# 3-1.net
KiCad netlist of a schematic drawn in Altium Designer
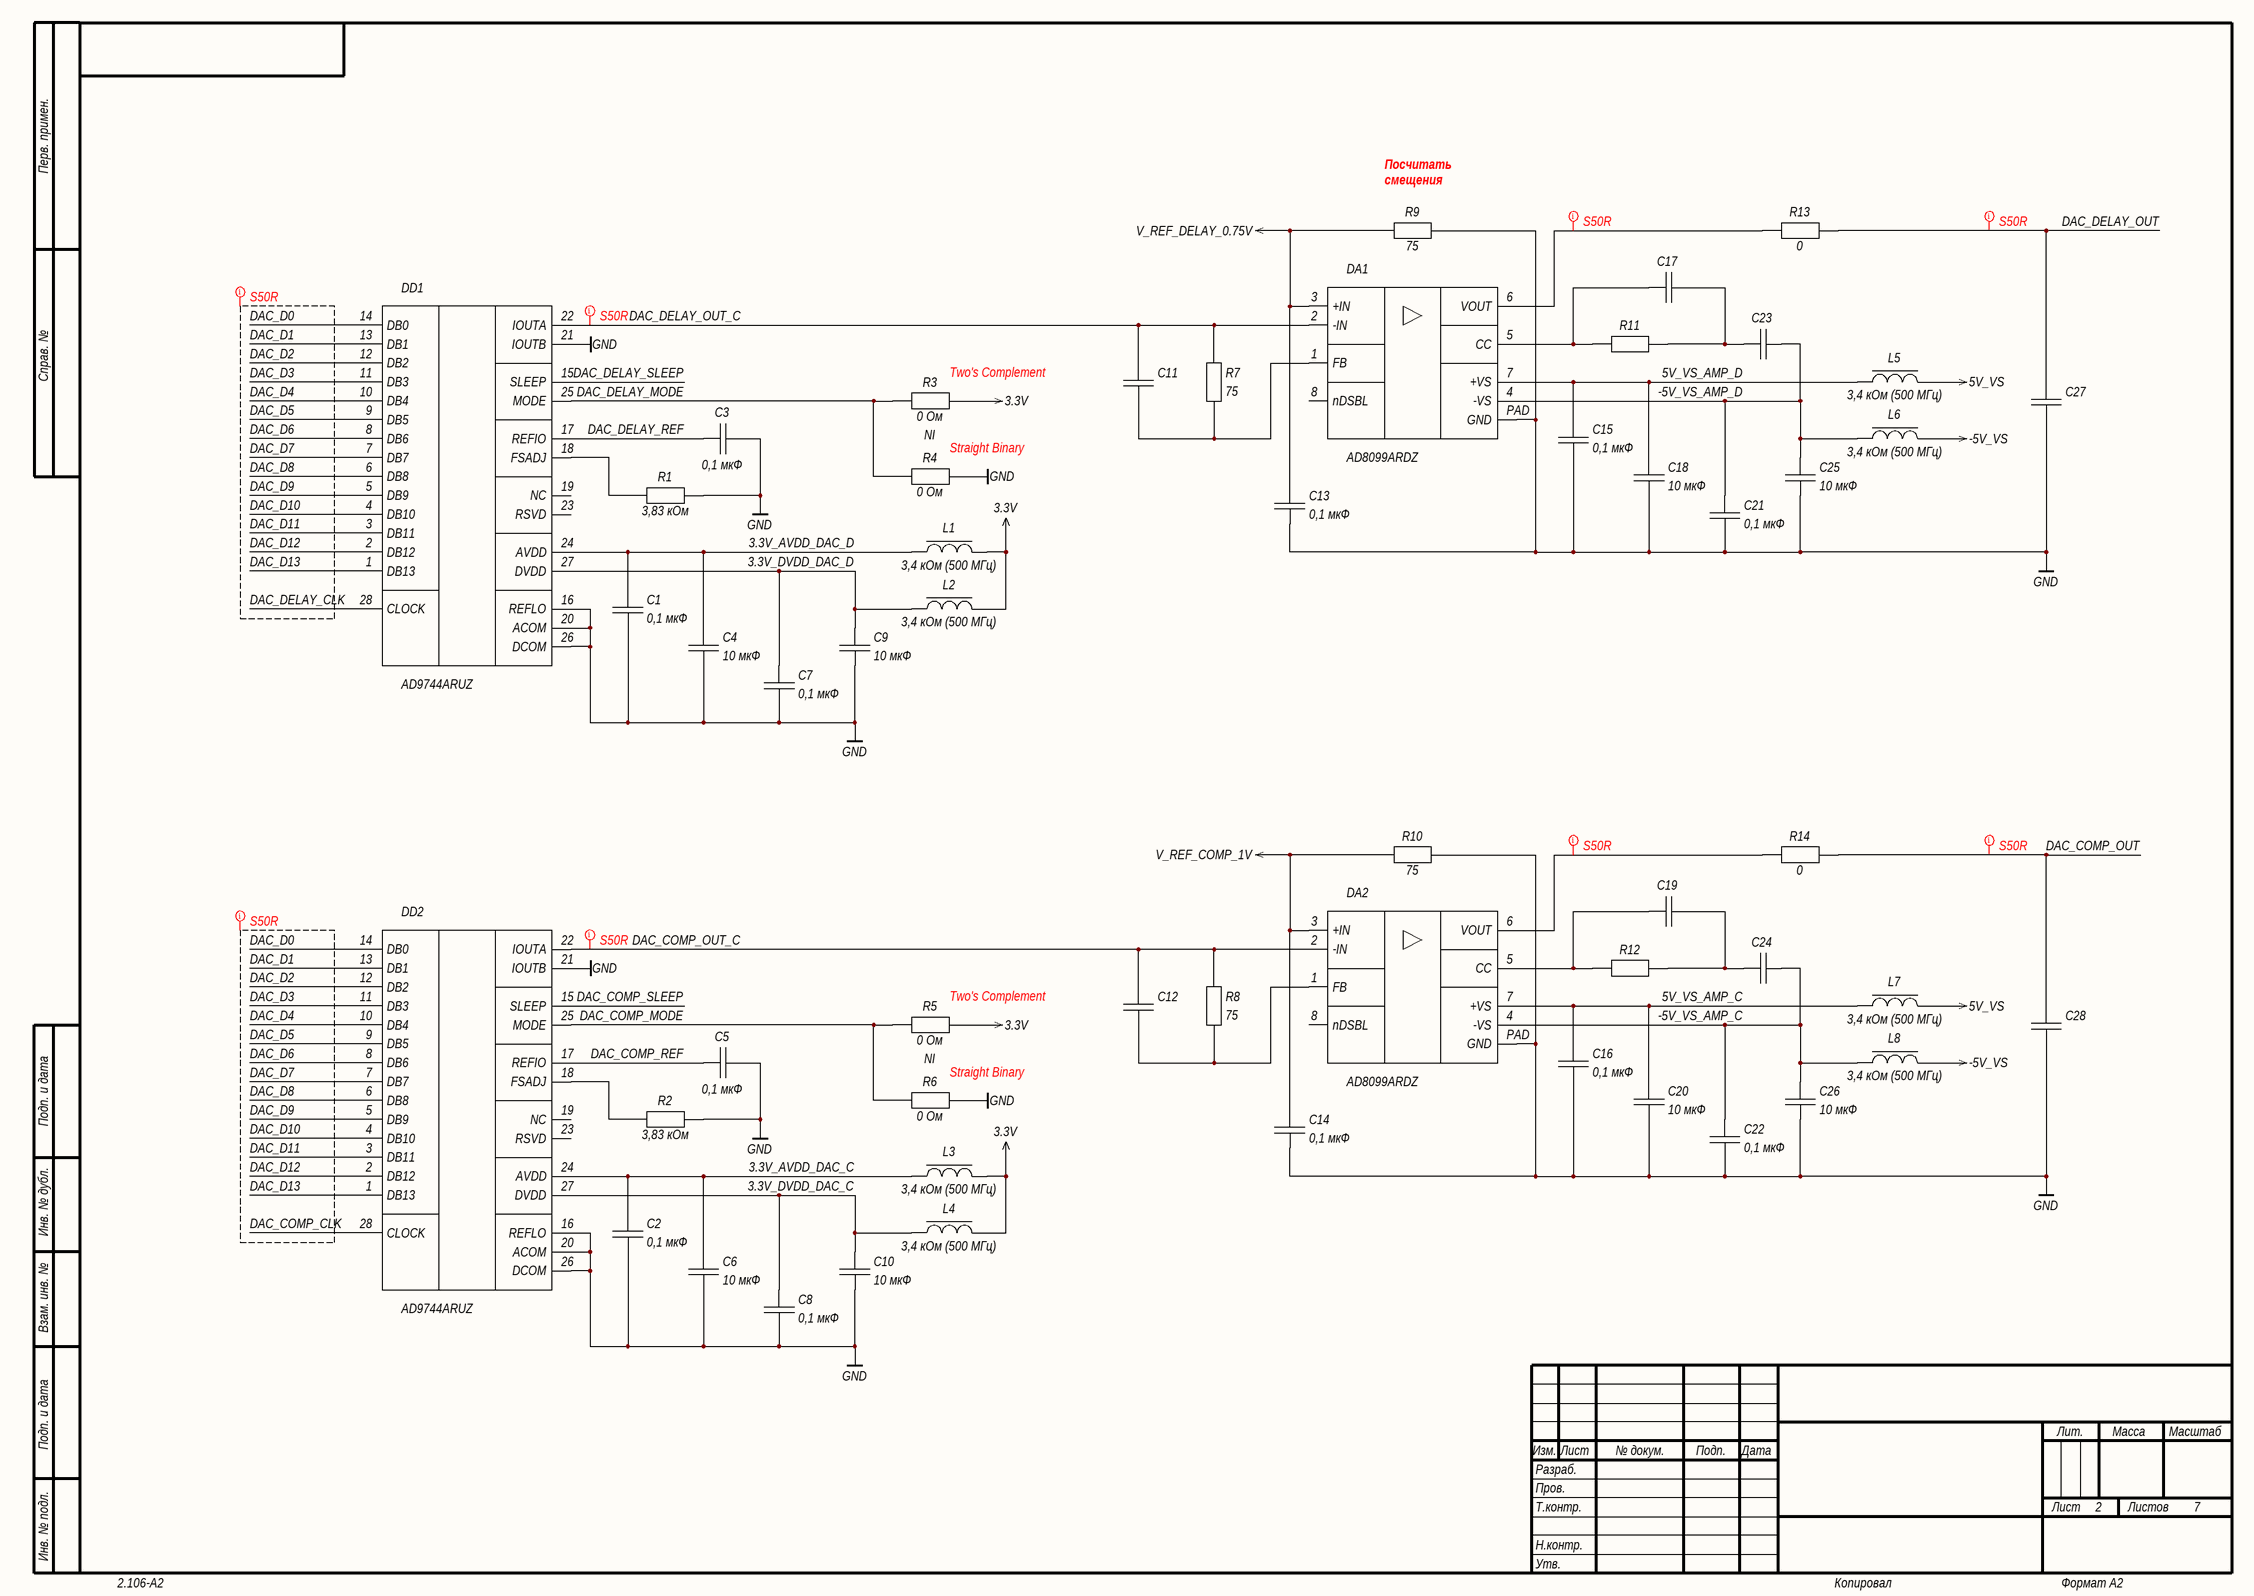
[diagram p0: Э3-1 УВ ЦАП.SchDoc]

(export (version "E")
  (design (tool "Eeschema 10.0.6"))
  (components
    (comp (ref "C1")
      (value "0,1 мкФ")
      (footprint "C0402-B-0.5mm")
      (description "0402 X7R 0,1 мкФ ±10 % 50 В")
      (fields (field (name "PARTNUMBER") "GRM155R71H104KE14D"))
      (libsource (lib "Capacitors") (part "Non Polar Ver."))
    )
    (comp (ref "C2")
      (value "0,1 мкФ")
      (footprint "C0402-B-0.5mm")
      (description "0402 X7R 0,1 мкФ ±10 % 50 В")
      (fields (field (name "PARTNUMBER") "GRM155R71H104KE14D"))
      (libsource (lib "Capacitors") (part "Non Polar Ver."))
    )
    (comp (ref "C3")
      (value "0,1 мкФ")
      (footprint "C0402-B-0.5mm")
      (description "0402 X7R 0,1 мкФ ±10 % 50 В")
      (fields (field (name "PARTNUMBER") "GRM155R71H104KE14D"))
      (libsource (lib "Capacitors") (part "Non Polar Hor."))
    )
    (comp (ref "C4")
      (value "10 мкФ")
      (footprint "C0603-B-0.8mm")
      (description "0603 X5R 10 мкФ ±20 % 25 В")
      (fields (field (name "PARTNUMBER") "GRM188R61E106MA73"))
      (libsource (lib "Capacitors") (part "Non Polar Ver."))
    )
    (comp (ref "C5")
      (value "0,1 мкФ")
      (footprint "C0402-B-0.5mm")
      (description "0402 X7R 0,1 мкФ ±10 % 50 В")
      (fields (field (name "PARTNUMBER") "GRM155R71H104KE14D"))
      (libsource (lib "Capacitors") (part "Non Polar Hor."))
    )
    (comp (ref "C6")
      (value "10 мкФ")
      (footprint "C0603-B-0.8mm")
      (description "0603 X5R 10 мкФ ±20 % 25 В")
      (fields (field (name "PARTNUMBER") "GRM188R61E106MA73"))
      (libsource (lib "Capacitors") (part "Non Polar Ver."))
    )
    (comp (ref "C7")
      (value "0,1 мкФ")
      (footprint "C0402-B-0.5mm")
      (description "0402 X7R 0,1 мкФ ±10 % 50 В")
      (fields (field (name "PARTNUMBER") "GRM155R71H104KE14D"))
      (libsource (lib "Capacitors") (part "Non Polar Ver."))
    )
    (comp (ref "C8")
      (value "0,1 мкФ")
      (footprint "C0402-B-0.5mm")
      (description "0402 X7R 0,1 мкФ ±10 % 50 В")
      (fields (field (name "PARTNUMBER") "GRM155R71H104KE14D"))
      (libsource (lib "Capacitors") (part "Non Polar Ver."))
    )
    (comp (ref "C9")
      (value "10 мкФ")
      (footprint "C0603-B-0.8mm")
      (description "0603 X5R 10 мкФ ±20 % 25 В")
      (fields (field (name "PARTNUMBER") "GRM188R61E106MA73"))
      (libsource (lib "Capacitors") (part "Non Polar Ver."))
    )
    (comp (ref "C10")
      (value "10 мкФ")
      (footprint "C0603-B-0.8mm")
      (description "GRM188R61E106MA73")
      (libsource (lib "Capacitors") (part "Non Polar Ver."))
    )
    (comp (ref "C11")
      (value "~")
      (footprint "C0402-B-0.5mm")
      (libsource (lib "Capacitors") (part "Non Polar Ver."))
    )
    (comp (ref "C12")
      (value "~")
      (footprint "C0402-B-0.5mm")
      (libsource (lib "Capacitors") (part "Non Polar Ver."))
    )
    (comp (ref "C13")
      (value "0,1 мкФ")
      (footprint "C0402-B-0.5mm")
      (description "0402 X7R 0,1 мкФ ±10 % 50 В")
      (fields (field (name "PARTNUMBER") "GRM155R71H104KE14D"))
      (libsource (lib "Capacitors") (part "Non Polar Ver."))
    )
    (comp (ref "C14")
      (value "0,1 мкФ")
      (footprint "C0402-B-0.5mm")
      (description "0402 X7R 0,1 мкФ ±10 % 50 В")
      (fields (field (name "PARTNUMBER") "GRM155R71H104KE14D"))
      (libsource (lib "Capacitors") (part "Non Polar Ver."))
    )
    (comp (ref "C15")
      (value "0,1 мкФ")
      (footprint "C0402-B-0.5mm")
      (description "0402 X7R 0,1 мкФ ±10 % 50 В")
      (fields (field (name "PARTNUMBER") "GRM155R71H104KE14D"))
      (libsource (lib "Capacitors") (part "Non Polar Ver."))
    )
    (comp (ref "C16")
      (value "0,1 мкФ")
      (footprint "C0402-B-0.5mm")
      (description "0402 X7R 0,1 мкФ ±10 % 50 В")
      (fields (field (name "PARTNUMBER") "GRM155R71H104KE14D"))
      (libsource (lib "Capacitors") (part "Non Polar Ver."))
    )
    (comp (ref "C17")
      (value "~")
      (footprint "C0402-B-0.5mm")
      (libsource (lib "Capacitors") (part "Non Polar Hor."))
    )
    (comp (ref "C18")
      (value "10 мкФ")
      (footprint "C0603-B-0.8mm")
      (description "0603 X5R 10 мкФ ±20 % 25 В")
      (fields (field (name "PARTNUMBER") "GRM188R61E106MA73"))
      (libsource (lib "Capacitors") (part "Non Polar Ver."))
    )
    (comp (ref "C19")
      (value "~")
      (footprint "C0402-B-0.5mm")
      (libsource (lib "Capacitors") (part "Non Polar Hor."))
    )
    (comp (ref "C20")
      (value "10 мкФ")
      (footprint "C0603-B-0.8mm")
      (description "0603 X5R 10 мкФ ±20 % 25 В")
      (fields (field (name "PARTNUMBER") "GRM188R61E106MA73"))
      (libsource (lib "Capacitors") (part "Non Polar Ver."))
    )
    (comp (ref "C21")
      (value "0,1 мкФ")
      (footprint "C0402-B-0.5mm")
      (description "0402 X7R 0,1 мкФ ±10 % 50 В")
      (fields (field (name "PARTNUMBER") "GRM155R71H104KE14D"))
      (libsource (lib "Capacitors") (part "Non Polar Ver."))
    )
    (comp (ref "C22")
      (value "0,1 мкФ")
      (footprint "C0402-B-0.5mm")
      (description "0402 X7R 0,1 мкФ ±10 % 50 В")
      (fields (field (name "PARTNUMBER") "GRM155R71H104KE14D"))
      (libsource (lib "Capacitors") (part "Non Polar Ver."))
    )
    (comp (ref "C23")
      (value "~")
      (footprint "C0402-B-0.5mm")
      (libsource (lib "Capacitors") (part "Non Polar Hor."))
    )
    (comp (ref "C24")
      (value "~")
      (footprint "C0402-B-0.5mm")
      (libsource (lib "Capacitors") (part "Non Polar Hor."))
    )
    (comp (ref "C25")
      (value "10 мкФ")
      (footprint "C0603-B-0.8mm")
      (description "0603 X5R 10 мкФ ±20 % 25 В")
      (fields (field (name "PARTNUMBER") "GRM188R61E106MA73"))
      (libsource (lib "Capacitors") (part "Non Polar Ver."))
    )
    (comp (ref "C26")
      (value "10 мкФ")
      (footprint "C0603-B-0.8mm")
      (description "0603 X5R 10 мкФ ±20 % 25 В")
      (fields (field (name "PARTNUMBER") "GRM188R61E106MA73"))
      (libsource (lib "Capacitors") (part "Non Polar Ver."))
    )
    (comp (ref "C27")
      (value "~")
      (footprint "C0402-B-0.5mm")
      (libsource (lib "Capacitors") (part "Non Polar Ver."))
    )
    (comp (ref "C28")
      (value "~")
      (footprint "C0402-B-0.5mm")
      (libsource (lib "Capacitors") (part "Non Polar Ver."))
    )
    (comp (ref "DA1")
      (value "AD8099ARDZ")
      (footprint "8-SOIC-EP-3.9")
      (description "Ultralow Distortion, High Speed, 0.95 nV/√Hz Voltage Noise Op Amp")
      (fields (field (name "MANUFACTURER") "Analog Devices, Inc."))
      (libsource (lib "Analog") (part "AD8099ARDZ"))
    )
    (comp (ref "DA2")
      (value "AD8099ARDZ")
      (footprint "8-SOIC-EP-3.9")
      (description "Ultralow Distortion, High Speed, 0.95 nV/√Hz Voltage Noise Op Amp")
      (fields (field (name "MANUFACTURER") "Analog Devices, Inc."))
      (libsource (lib "Analog") (part "AD8099ARDZ"))
    )
    (comp (ref "DD1")
      (value "AD9744ARUZ")
      (footprint "28-TSSOP-4.4")
      (description "14-Bit, 210 MSPS TxDAC®\r\nD/A Converter")
      (fields (field (name "MANUFACTURER") "Analog Devices"))
      (libsource (lib "Digital") (part "AD9744ARUZ"))
    )
    (comp (ref "DD2")
      (value "AD9744ARUZ")
      (footprint "28-TSSOP-4.4")
      (description "14-Bit, 210 MSPS TxDAC®\r\nD/A Converter")
      (fields (field (name "MANUFACTURER") "Analog Devices"))
      (libsource (lib "Digital") (part "AD9744ARUZ"))
    )
    (comp (ref "L1")
      (value "3,4 кОм (500 МГц)")
      (footprint "L0402-B-0.5mm")
      (fields (field (name "PARTNUMBER") "BLM15HD182BH1"))
      (libsource (lib "Inductors") (part "Inductor MC Hor."))
    )
    (comp (ref "L2")
      (value "3,4 кОм (500 МГц)")
      (footprint "L0402-B-0.5mm")
      (fields (field (name "PARTNUMBER") "BLM15HD182BH1"))
      (libsource (lib "Inductors") (part "Inductor MC Hor."))
    )
    (comp (ref "L3")
      (value "3,4 кОм (500 МГц)")
      (footprint "L0402-B-0.5mm")
      (fields (field (name "PARTNUMBER") "BLM15HD182BH1"))
      (libsource (lib "Inductors") (part "Inductor MC Hor."))
    )
    (comp (ref "L4")
      (value "3,4 кОм (500 МГц)")
      (footprint "L0402-B-0.5mm")
      (fields (field (name "PARTNUMBER") "BLM15HD182BH1"))
      (libsource (lib "Inductors") (part "Inductor MC Hor."))
    )
    (comp (ref "L5")
      (value "3,4 кОм (500 МГц)")
      (footprint "L0402-B-0.5mm")
      (fields (field (name "PARTNUMBER") "BLM15HD182BH1"))
      (libsource (lib "Inductors") (part "Inductor MC Hor."))
    )
    (comp (ref "L6")
      (value "3,4 кОм (500 МГц)")
      (footprint "L0402-B-0.5mm")
      (fields (field (name "PARTNUMBER") "BLM15HD182BH1"))
      (libsource (lib "Inductors") (part "Inductor MC Hor."))
    )
    (comp (ref "L7")
      (value "3,4 кОм (500 МГц)")
      (footprint "L0402-B-0.5mm")
      (fields (field (name "PARTNUMBER") "BLM15HD182BH1"))
      (libsource (lib "Inductors") (part "Inductor MC Hor."))
    )
    (comp (ref "L8")
      (value "3,4 кОм (500 МГц)")
      (footprint "L0402-B-0.5mm")
      (fields (field (name "PARTNUMBER") "BLM15HD182BH1"))
      (libsource (lib "Inductors") (part "Inductor MC Hor."))
    )
    (comp (ref "R1")
      (value "3,83 кОм")
      (footprint "CR0402-B-0.35mm")
      (description "0402 3,83 кОм ±1 %")
      (libsource (lib "Resistors") (part "Resistor Hor."))
    )
    (comp (ref "R2")
      (value "3,83 кОм")
      (footprint "CR0402-B-0.35mm")
      (description "0402 3,83 кОм ±1 %")
      (libsource (lib "Resistors") (part "Resistor Hor."))
    )
    (comp (ref "R3")
      (value "0 Ом")
      (footprint "CR0402-B-0.35mm")
      (description "0402 0 Ом")
      (fields (field (name "COMPONENTTYPE") "NI"))
      (libsource (lib "Resistors") (part "Resistor Hor."))
    )
    (comp (ref "R4")
      (value "0 Ом")
      (footprint "CR0402-B-0.35mm")
      (libsource (lib "Resistors") (part "Resistor Hor."))
    )
    (comp (ref "R5")
      (value "0 Ом")
      (footprint "CR0402-B-0.35mm")
      (description "0402 0 Ом")
      (fields (field (name "COMPONENTTYPE") "NI"))
      (libsource (lib "Resistors") (part "Resistor Hor."))
    )
    (comp (ref "R6")
      (value "0 Ом")
      (footprint "CR0402-B-0.35mm")
      (libsource (lib "Resistors") (part "Resistor Hor."))
    )
    (comp (ref "R7")
      (value "75")
      (footprint "CR0402-B-0.35mm")
      (description "0402 75 Ом ±1 %")
      (libsource (lib "Resistors") (part "Resistor Ver."))
    )
    (comp (ref "R8")
      (value "75")
      (footprint "CR0402-B-0.35mm")
      (description "0402 75 Ом ±1 %")
      (libsource (lib "Resistors") (part "Resistor Ver."))
    )
    (comp (ref "R9")
      (value "75")
      (footprint "CR0402-B-0.35mm")
      (description "0402 75 Ом ±1 %")
      (libsource (lib "Resistors") (part "Resistor Hor."))
    )
    (comp (ref "R10")
      (value "75")
      (footprint "CR0402-B-0.35mm")
      (description "0402 75 Ом ±1 %")
      (libsource (lib "Resistors") (part "Resistor Hor."))
    )
    (comp (ref "R11")
      (value "~")
      (footprint "CR0402-B-0.35mm")
      (libsource (lib "Resistors") (part "Resistor Hor."))
    )
    (comp (ref "R12")
      (value "~")
      (footprint "CR0402-B-0.35mm")
      (libsource (lib "Resistors") (part "Resistor Hor."))
    )
    (comp (ref "R13")
      (value "0")
      (footprint "CR0402-B-0.35mm")
      (description "0402 0 Ом")
      (libsource (lib "Resistors") (part "Resistor Hor."))
    )
    (comp (ref "R14")
      (value "0")
      (footprint "CR0402-B-0.35mm")
      (description "0402 0 Ом")
      (libsource (lib "Resistors") (part "Resistor Hor."))
    )
  )
  (nets
    (net (code "1") (name "-5V_VS") (class "Default")
      (node (ref "L6") (pin "2") (pinfunction "2_2") (pintype "passive"))
      (node (ref "L8") (pin "2") (pinfunction "2_2") (pintype "passive"))
    )
    (net (code "2") (name "/-5V_VS_AMP_C") (class "Default")
      (node (ref "C22") (pin "1") (pinfunction "1_1") (pintype "passive"))
      (node (ref "C24") (pin "2") (pinfunction "2_2") (pintype "passive"))
      (node (ref "C26") (pin "1") (pinfunction "1_1") (pintype "passive"))
      (node (ref "DA2") (pin "4") (pinfunction "-VS_4") (pintype "passive"))
      (node (ref "L8") (pin "1") (pinfunction "1_1") (pintype "passive"))
    )
    (net (code "3") (name "/-5V_VS_AMP_D") (class "Default")
      (node (ref "C21") (pin "1") (pinfunction "1_1") (pintype "passive"))
      (node (ref "C23") (pin "2") (pinfunction "2_2") (pintype "passive"))
      (node (ref "C25") (pin "1") (pinfunction "1_1") (pintype "passive"))
      (node (ref "DA1") (pin "4") (pinfunction "-VS_4") (pintype "passive"))
      (node (ref "L6") (pin "1") (pinfunction "1_1") (pintype "passive"))
    )
    (net (code "4") (name "/3.3V_AVDD_DAC_C") (class "Default")
      (node (ref "C2") (pin "1") (pinfunction "1_1") (pintype "passive"))
      (node (ref "C6") (pin "1") (pinfunction "1_1") (pintype "passive"))
      (node (ref "DD2") (pin "24") (pinfunction "AVDD_24") (pintype "passive"))
      (node (ref "L3") (pin "1") (pinfunction "1_1") (pintype "passive"))
    )
    (net (code "5") (name "/3.3V_AVDD_DAC_D") (class "Default")
      (node (ref "C1") (pin "1") (pinfunction "1_1") (pintype "passive"))
      (node (ref "C4") (pin "1") (pinfunction "1_1") (pintype "passive"))
      (node (ref "DD1") (pin "24") (pinfunction "AVDD_24") (pintype "passive"))
      (node (ref "L1") (pin "1") (pinfunction "1_1") (pintype "passive"))
    )
    (net (code "6") (name "/3.3V_DVDD_DAC_C") (class "Default")
      (node (ref "C10") (pin "1") (pinfunction "1_1") (pintype "passive"))
      (node (ref "C8") (pin "1") (pinfunction "1_1") (pintype "passive"))
      (node (ref "DD2") (pin "27") (pinfunction "DVDD_27") (pintype "passive"))
      (node (ref "L4") (pin "1") (pinfunction "1_1") (pintype "passive"))
    )
    (net (code "7") (name "/3.3V_DVDD_DAC_D") (class "Default")
      (node (ref "C7") (pin "1") (pinfunction "1_1") (pintype "passive"))
      (node (ref "C9") (pin "1") (pinfunction "1_1") (pintype "passive"))
      (node (ref "DD1") (pin "27") (pinfunction "DVDD_27") (pintype "passive"))
      (node (ref "L2") (pin "1") (pinfunction "1_1") (pintype "passive"))
    )
    (net (code "8") (name "/5V_VS_AMP_C") (class "Default")
      (node (ref "C16") (pin "1") (pinfunction "1_1") (pintype "passive"))
      (node (ref "C20") (pin "1") (pinfunction "1_1") (pintype "passive"))
      (node (ref "DA2") (pin "7") (pinfunction "+VS_7") (pintype "passive"))
      (node (ref "L7") (pin "1") (pinfunction "1_1") (pintype "passive"))
    )
    (net (code "9") (name "/5V_VS_AMP_D") (class "Default")
      (node (ref "C15") (pin "1") (pinfunction "1_1") (pintype "passive"))
      (node (ref "C18") (pin "1") (pinfunction "1_1") (pintype "passive"))
      (node (ref "DA1") (pin "7") (pinfunction "+VS_7") (pintype "passive"))
      (node (ref "L5") (pin "1") (pinfunction "1_1") (pintype "passive"))
    )
    (net (code "10") (name "/DAC_COMP_CLK") (class "Default")
      (node (ref "DD2") (pin "28") (pinfunction "CLOCK_28") (pintype "passive"))
    )
    (net (code "11") (name "/DAC_COMP_MODE") (class "Default")
      (node (ref "DD2") (pin "25") (pinfunction "MODE_25") (pintype "passive"))
      (node (ref "R5") (pin "1") (pinfunction "1_1") (pintype "passive"))
      (node (ref "R6") (pin "1") (pinfunction "1_1") (pintype "passive"))
    )
    (net (code "12") (name "/DAC_COMP_OUT") (class "Default")
      (node (ref "C28") (pin "1") (pinfunction "1_1") (pintype "passive"))
      (node (ref "R14") (pin "2") (pinfunction "2_2") (pintype "passive"))
    )
    (net (code "13") (name "/DAC_COMP_OUT_C") (class "Default")
      (node (ref "C12") (pin "1") (pinfunction "1_1") (pintype "passive"))
      (node (ref "DA2") (pin "2") (pinfunction "-IN_2") (pintype "passive"))
      (node (ref "DD2") (pin "22") (pinfunction "IOUTA_22") (pintype "passive"))
      (node (ref "R8") (pin "1") (pinfunction "1_1") (pintype "passive"))
    )
    (net (code "14") (name "/DAC_COMP_REF") (class "Default")
      (node (ref "C5") (pin "1") (pinfunction "1_1") (pintype "passive"))
      (node (ref "DD2") (pin "17") (pinfunction "REFIO_17") (pintype "passive"))
    )
    (net (code "15") (name "/DAC_COMP_SLEEP") (class "Default")
      (node (ref "DD2") (pin "15") (pinfunction "SLEEP_15") (pintype "passive"))
    )
    (net (code "16") (name "/DAC_D0") (class "Default")
      (node (ref "DD1") (pin "14") (pinfunction "DB0_14") (pintype "passive"))
      (node (ref "DD2") (pin "14") (pinfunction "DB0_14") (pintype "passive"))
    )
    (net (code "17") (name "/DAC_D1") (class "Default")
      (node (ref "DD1") (pin "13") (pinfunction "DB1_13") (pintype "passive"))
      (node (ref "DD2") (pin "13") (pinfunction "DB1_13") (pintype "passive"))
    )
    (net (code "18") (name "/DAC_D2") (class "Default")
      (node (ref "DD1") (pin "12") (pinfunction "DB2_12") (pintype "passive"))
      (node (ref "DD2") (pin "12") (pinfunction "DB2_12") (pintype "passive"))
    )
    (net (code "19") (name "/DAC_D3") (class "Default")
      (node (ref "DD1") (pin "11") (pinfunction "DB3_11") (pintype "passive"))
      (node (ref "DD2") (pin "11") (pinfunction "DB3_11") (pintype "passive"))
    )
    (net (code "20") (name "/DAC_D4") (class "Default")
      (node (ref "DD1") (pin "10") (pinfunction "DB4_10") (pintype "passive"))
      (node (ref "DD2") (pin "10") (pinfunction "DB4_10") (pintype "passive"))
    )
    (net (code "21") (name "/DAC_D5") (class "Default")
      (node (ref "DD1") (pin "9") (pinfunction "DB5_9") (pintype "passive"))
      (node (ref "DD2") (pin "9") (pinfunction "DB5_9") (pintype "passive"))
    )
    (net (code "22") (name "/DAC_D6") (class "Default")
      (node (ref "DD1") (pin "8") (pinfunction "DB6_8") (pintype "passive"))
      (node (ref "DD2") (pin "8") (pinfunction "DB6_8") (pintype "passive"))
    )
    (net (code "23") (name "/DAC_D7") (class "Default")
      (node (ref "DD1") (pin "7") (pinfunction "DB7_7") (pintype "passive"))
      (node (ref "DD2") (pin "7") (pinfunction "DB7_7") (pintype "passive"))
    )
    (net (code "24") (name "/DAC_D8") (class "Default")
      (node (ref "DD1") (pin "6") (pinfunction "DB8_6") (pintype "passive"))
      (node (ref "DD2") (pin "6") (pinfunction "DB8_6") (pintype "passive"))
    )
    (net (code "25") (name "/DAC_D9") (class "Default")
      (node (ref "DD1") (pin "5") (pinfunction "DB9_5") (pintype "passive"))
      (node (ref "DD2") (pin "5") (pinfunction "DB9_5") (pintype "passive"))
    )
    (net (code "26") (name "/DAC_D10") (class "Default")
      (node (ref "DD1") (pin "4") (pinfunction "DB10_4") (pintype "passive"))
      (node (ref "DD2") (pin "4") (pinfunction "DB10_4") (pintype "passive"))
    )
    (net (code "27") (name "/DAC_D11") (class "Default")
      (node (ref "DD1") (pin "3") (pinfunction "DB11_3") (pintype "passive"))
      (node (ref "DD2") (pin "3") (pinfunction "DB11_3") (pintype "passive"))
    )
    (net (code "28") (name "/DAC_D12") (class "Default")
      (node (ref "DD1") (pin "2") (pinfunction "DB12_2") (pintype "passive"))
      (node (ref "DD2") (pin "2") (pinfunction "DB12_2") (pintype "passive"))
    )
    (net (code "29") (name "/DAC_D13") (class "Default")
      (node (ref "DD1") (pin "1") (pinfunction "DB13_1") (pintype "passive"))
      (node (ref "DD2") (pin "1") (pinfunction "DB13_1") (pintype "passive"))
    )
    (net (code "30") (name "/DAC_DELAY_CLK") (class "Default")
      (node (ref "DD1") (pin "28") (pinfunction "CLOCK_28") (pintype "passive"))
    )
    (net (code "31") (name "/DAC_DELAY_MODE") (class "Default")
      (node (ref "DD1") (pin "25") (pinfunction "MODE_25") (pintype "passive"))
      (node (ref "R3") (pin "1") (pinfunction "1_1") (pintype "passive"))
      (node (ref "R4") (pin "1") (pinfunction "1_1") (pintype "passive"))
    )
    (net (code "32") (name "/DAC_DELAY_OUT") (class "Default")
      (node (ref "C27") (pin "1") (pinfunction "1_1") (pintype "passive"))
      (node (ref "R13") (pin "2") (pinfunction "2_2") (pintype "passive"))
    )
    (net (code "33") (name "/DAC_DELAY_OUT_C") (class "Default")
      (node (ref "C11") (pin "1") (pinfunction "1_1") (pintype "passive"))
      (node (ref "DA1") (pin "2") (pinfunction "-IN_2") (pintype "passive"))
      (node (ref "DD1") (pin "22") (pinfunction "IOUTA_22") (pintype "passive"))
      (node (ref "R7") (pin "1") (pinfunction "1_1") (pintype "passive"))
    )
    (net (code "34") (name "/DAC_DELAY_REF") (class "Default")
      (node (ref "C3") (pin "1") (pinfunction "1_1") (pintype "passive"))
      (node (ref "DD1") (pin "17") (pinfunction "REFIO_17") (pintype "passive"))
    )
    (net (code "35") (name "/DAC_DELAY_SLEEP") (class "Default")
      (node (ref "DD1") (pin "15") (pinfunction "SLEEP_15") (pintype "passive"))
    )
    (net (code "36") (name "3.3V") (class "Default")
      (node (ref "L1") (pin "2") (pinfunction "2_2") (pintype "passive"))
      (node (ref "L2") (pin "2") (pinfunction "2_2") (pintype "passive"))
      (node (ref "L3") (pin "2") (pinfunction "2_2") (pintype "passive"))
      (node (ref "L4") (pin "2") (pinfunction "2_2") (pintype "passive"))
      (node (ref "R3") (pin "2") (pinfunction "2_2") (pintype "passive"))
      (node (ref "R5") (pin "2") (pinfunction "2_2") (pintype "passive"))
    )
    (net (code "37") (name "5V_VS") (class "Default")
      (node (ref "L5") (pin "2") (pinfunction "2_2") (pintype "passive"))
      (node (ref "L7") (pin "2") (pinfunction "2_2") (pintype "passive"))
    )
    (net (code "38") (name "GND") (class "Default")
      (node (ref "C1") (pin "2") (pinfunction "2_2") (pintype "passive"))
      (node (ref "C10") (pin "2") (pinfunction "2_2") (pintype "passive"))
      (node (ref "C13") (pin "2") (pinfunction "2_2") (pintype "passive"))
      (node (ref "C14") (pin "2") (pinfunction "2_2") (pintype "passive"))
      (node (ref "C15") (pin "2") (pinfunction "2_2") (pintype "passive"))
      (node (ref "C16") (pin "2") (pinfunction "2_2") (pintype "passive"))
      (node (ref "C18") (pin "2") (pinfunction "2_2") (pintype "passive"))
      (node (ref "C2") (pin "2") (pinfunction "2_2") (pintype "passive"))
      (node (ref "C20") (pin "2") (pinfunction "2_2") (pintype "passive"))
      (node (ref "C21") (pin "2") (pinfunction "2_2") (pintype "passive"))
      (node (ref "C22") (pin "2") (pinfunction "2_2") (pintype "passive"))
      (node (ref "C25") (pin "2") (pinfunction "2_2") (pintype "passive"))
      (node (ref "C26") (pin "2") (pinfunction "2_2") (pintype "passive"))
      (node (ref "C27") (pin "2") (pinfunction "2_2") (pintype "passive"))
      (node (ref "C28") (pin "2") (pinfunction "2_2") (pintype "passive"))
      (node (ref "C3") (pin "2") (pinfunction "2_2") (pintype "passive"))
      (node (ref "C4") (pin "2") (pinfunction "2_2") (pintype "passive"))
      (node (ref "C5") (pin "2") (pinfunction "2_2") (pintype "passive"))
      (node (ref "C6") (pin "2") (pinfunction "2_2") (pintype "passive"))
      (node (ref "C7") (pin "2") (pinfunction "2_2") (pintype "passive"))
      (node (ref "C8") (pin "2") (pinfunction "2_2") (pintype "passive"))
      (node (ref "C9") (pin "2") (pinfunction "2_2") (pintype "passive"))
      (node (ref "DA1") (pin "PAD") (pinfunction "GND_PAD") (pintype "passive"))
      (node (ref "DA2") (pin "PAD") (pinfunction "GND_PAD") (pintype "passive"))
      (node (ref "DD1") (pin "16") (pinfunction "REFLO_16") (pintype "passive"))
      (node (ref "DD1") (pin "20") (pinfunction "ACOM_20") (pintype "passive"))
      (node (ref "DD1") (pin "21") (pinfunction "IOUTB_21") (pintype "passive"))
      (node (ref "DD1") (pin "26") (pinfunction "DCOM_26") (pintype "passive"))
      (node (ref "DD2") (pin "16") (pinfunction "REFLO_16") (pintype "passive"))
      (node (ref "DD2") (pin "20") (pinfunction "ACOM_20") (pintype "passive"))
      (node (ref "DD2") (pin "21") (pinfunction "IOUTB_21") (pintype "passive"))
      (node (ref "DD2") (pin "26") (pinfunction "DCOM_26") (pintype "passive"))
      (node (ref "R1") (pin "2") (pinfunction "2_2") (pintype "passive"))
      (node (ref "R10") (pin "2") (pinfunction "2_2") (pintype "passive"))
      (node (ref "R2") (pin "2") (pinfunction "2_2") (pintype "passive"))
      (node (ref "R4") (pin "2") (pinfunction "2_2") (pintype "passive"))
      (node (ref "R6") (pin "2") (pinfunction "2_2") (pintype "passive"))
      (node (ref "R9") (pin "2") (pinfunction "2_2") (pintype "passive"))
    )
    (net (code "39") (name "Net-(C17-Pad2)") (class "Default")
      (node (ref "C17") (pin "2") (pinfunction "2_2") (pintype "passive"))
      (node (ref "C23") (pin "1") (pinfunction "1_1") (pintype "passive"))
      (node (ref "R11") (pin "2") (pinfunction "2_2") (pintype "passive"))
    )
    (net (code "40") (name "Net-(C19-Pad2)") (class "Default")
      (node (ref "C19") (pin "2") (pinfunction "2_2") (pintype "passive"))
      (node (ref "C24") (pin "1") (pinfunction "1_1") (pintype "passive"))
      (node (ref "R12") (pin "2") (pinfunction "2_2") (pintype "passive"))
    )
    (net (code "41") (name "Net-(DA1-CC)") (class "Default")
      (node (ref "C17") (pin "1") (pinfunction "1_1") (pintype "passive"))
      (node (ref "DA1") (pin "5") (pinfunction "CC_5") (pintype "passive"))
      (node (ref "R11") (pin "1") (pinfunction "1_1") (pintype "passive"))
    )
    (net (code "42") (name "Net-(DA1-FB)") (class "Default")
      (node (ref "C11") (pin "2") (pinfunction "2_2") (pintype "passive"))
      (node (ref "DA1") (pin "1") (pinfunction "FB_1") (pintype "passive"))
      (node (ref "R7") (pin "2") (pinfunction "2_2") (pintype "passive"))
    )
    (net (code "43") (name "Net-(DA1-VOUT)") (class "Default")
      (node (ref "DA1") (pin "6") (pinfunction "VOUT_6") (pintype "passive"))
      (node (ref "R13") (pin "1") (pinfunction "1_1") (pintype "passive"))
    )
    (net (code "44") (name "Net-(DA2-CC)") (class "Default")
      (node (ref "C19") (pin "1") (pinfunction "1_1") (pintype "passive"))
      (node (ref "DA2") (pin "5") (pinfunction "CC_5") (pintype "passive"))
      (node (ref "R12") (pin "1") (pinfunction "1_1") (pintype "passive"))
    )
    (net (code "45") (name "Net-(DA2-FB)") (class "Default")
      (node (ref "C12") (pin "2") (pinfunction "2_2") (pintype "passive"))
      (node (ref "DA2") (pin "1") (pinfunction "FB_1") (pintype "passive"))
      (node (ref "R8") (pin "2") (pinfunction "2_2") (pintype "passive"))
    )
    (net (code "46") (name "Net-(DA2-VOUT)") (class "Default")
      (node (ref "DA2") (pin "6") (pinfunction "VOUT_6") (pintype "passive"))
      (node (ref "R14") (pin "1") (pinfunction "1_1") (pintype "passive"))
    )
    (net (code "47") (name "Net-(DD1-FSADJ)") (class "Default")
      (node (ref "DD1") (pin "18") (pinfunction "FSADJ_18") (pintype "passive"))
      (node (ref "R1") (pin "1") (pinfunction "1_1") (pintype "passive"))
    )
    (net (code "48") (name "Net-(DD2-FSADJ)") (class "Default")
      (node (ref "DD2") (pin "18") (pinfunction "FSADJ_18") (pintype "passive"))
      (node (ref "R2") (pin "1") (pinfunction "1_1") (pintype "passive"))
    )
    (net (code "49") (name "V_REF_COMP_1V") (class "Default")
      (node (ref "C14") (pin "1") (pinfunction "1_1") (pintype "passive"))
      (node (ref "DA2") (pin "3") (pinfunction "+IN_3") (pintype "passive"))
      (node (ref "R10") (pin "1") (pinfunction "1_1") (pintype "passive"))
    )
    (net (code "50") (name "V_REF_DELAY_0.75V") (class "Default")
      (node (ref "C13") (pin "1") (pinfunction "1_1") (pintype "passive"))
      (node (ref "DA1") (pin "3") (pinfunction "+IN_3") (pintype "passive"))
      (node (ref "R9") (pin "1") (pinfunction "1_1") (pintype "passive"))
    )
    (net (code "51") (name "unconnected-(DA1-nDSBL-Pad8)") (class "Default")
      (node (ref "DA1") (pin "8") (pinfunction "nDSBL_8") (pintype "passive"))
    )
    (net (code "52") (name "unconnected-(DA2-nDSBL-Pad8)") (class "Default")
      (node (ref "DA2") (pin "8") (pinfunction "nDSBL_8") (pintype "passive"))
    )
    (net (code "53") (name "unconnected-(DD1-NC-Pad19)") (class "Default")
      (node (ref "DD1") (pin "19") (pinfunction "NC_19") (pintype "passive"))
    )
    (net (code "54") (name "unconnected-(DD1-RSVD-Pad23)") (class "Default")
      (node (ref "DD1") (pin "23") (pinfunction "RSVD_23") (pintype "passive"))
    )
    (net (code "55") (name "unconnected-(DD2-NC-Pad19)") (class "Default")
      (node (ref "DD2") (pin "19") (pinfunction "NC_19") (pintype "passive"))
    )
    (net (code "56") (name "unconnected-(DD2-RSVD-Pad23)") (class "Default")
      (node (ref "DD2") (pin "23") (pinfunction "RSVD_23") (pintype "passive"))
    )
  )
)
